# sam3u_breakout.net
KiCad netlist of a schematic drawn in EAGLE
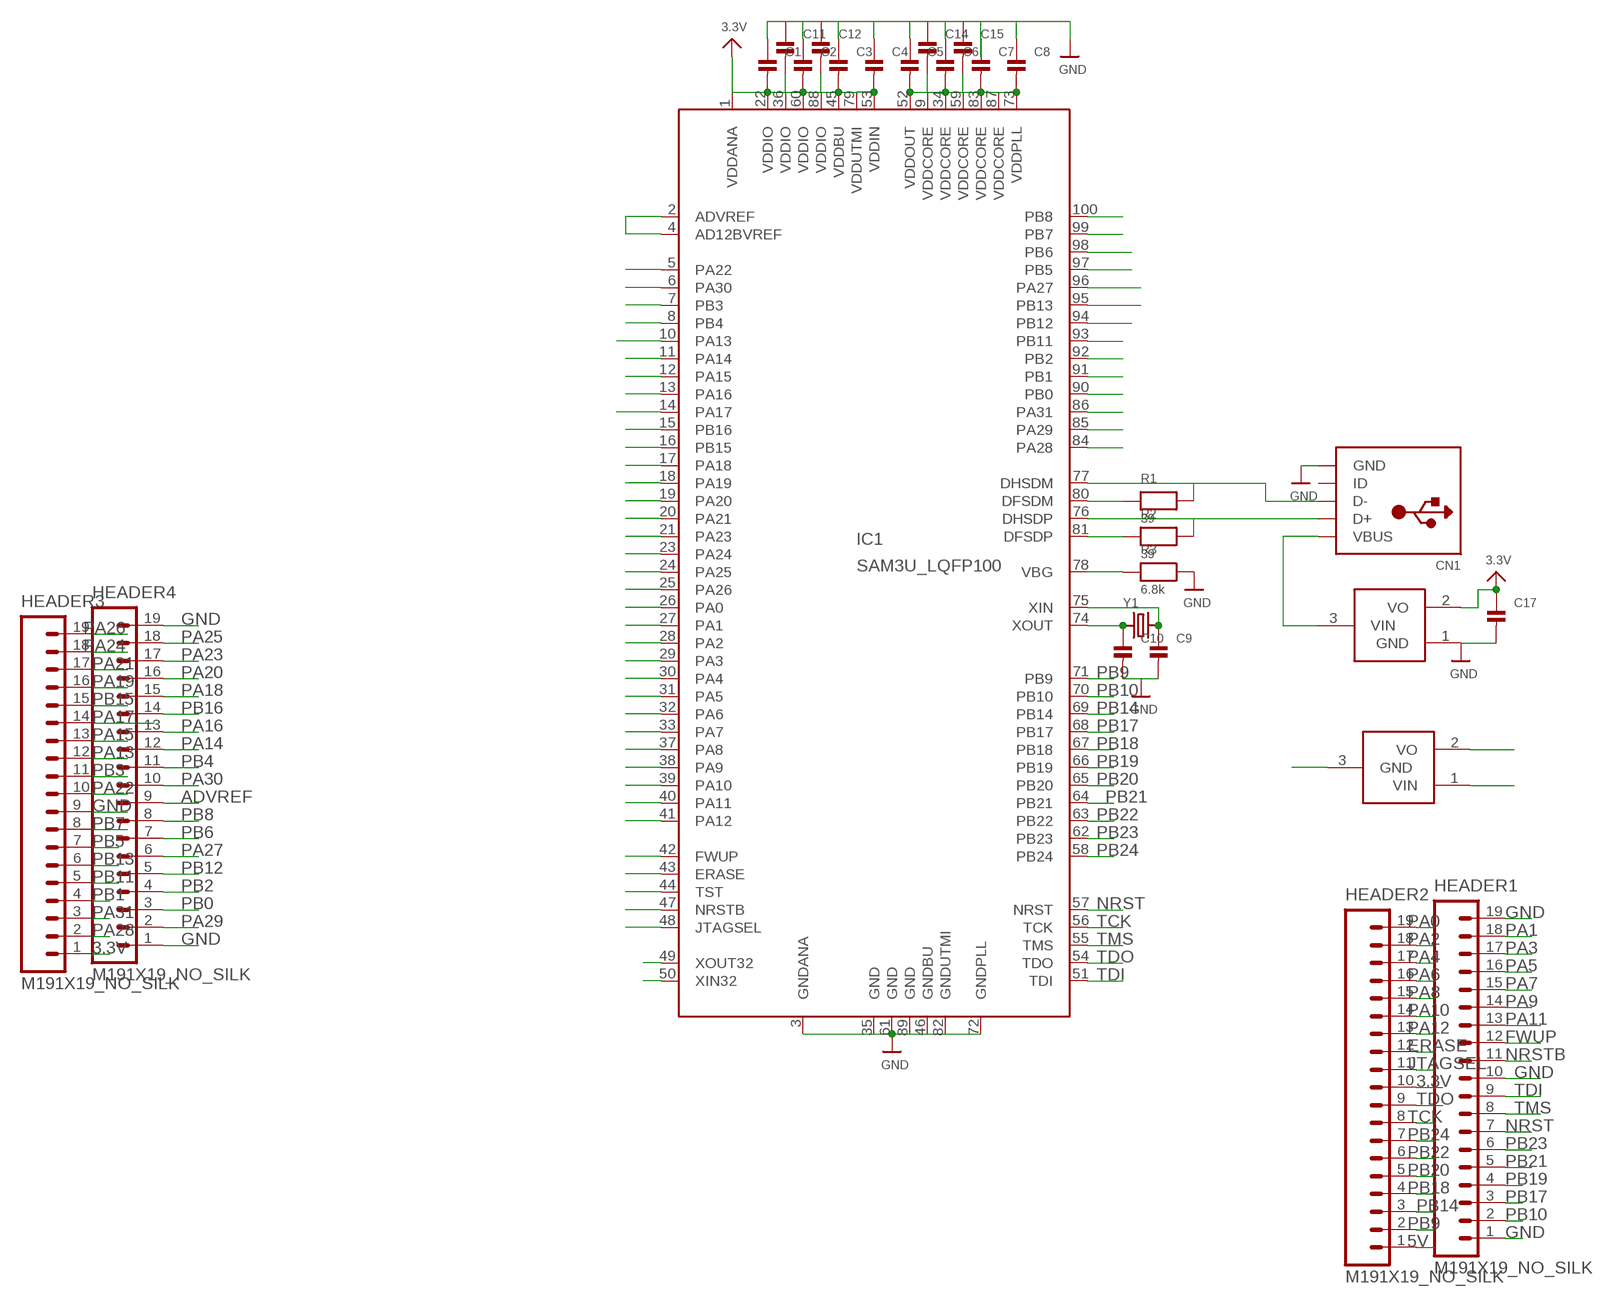
[diagram p0: schematic, sheet 1]

(export (version "E")
  (design (tool "Eeschema 10.0.6"))
  (components
    (comp (ref "C1")
      (value "CAP_CERAMIC0402")
      (footprint "eagle-import:0402")
      (libsource (lib "eagle-import") (part "CAP_CERAMIC0402"))
    )
    (comp (ref "C2")
      (value "CAP_CERAMIC0402")
      (footprint "eagle-import:0402")
      (libsource (lib "eagle-import") (part "CAP_CERAMIC0402"))
    )
    (comp (ref "C3")
      (value "CAP_CERAMIC0402")
      (footprint "eagle-import:0402")
      (libsource (lib "eagle-import") (part "CAP_CERAMIC0402"))
    )
    (comp (ref "C4")
      (value "CAP_CERAMIC0402")
      (footprint "eagle-import:0402")
      (libsource (lib "eagle-import") (part "CAP_CERAMIC0402"))
    )
    (comp (ref "C5")
      (value "CAP_CERAMIC0402")
      (footprint "eagle-import:0402")
      (libsource (lib "eagle-import") (part "CAP_CERAMIC0402"))
    )
    (comp (ref "C6")
      (value "CAP_CERAMIC0402")
      (footprint "eagle-import:0402")
      (libsource (lib "eagle-import") (part "CAP_CERAMIC0402"))
    )
    (comp (ref "C7")
      (value "CAP_CERAMIC0402")
      (footprint "eagle-import:0402")
      (libsource (lib "eagle-import") (part "CAP_CERAMIC0402"))
    )
    (comp (ref "C8")
      (value "CAP_CERAMIC0402")
      (footprint "eagle-import:0402")
      (libsource (lib "eagle-import") (part "CAP_CERAMIC0402"))
    )
    (comp (ref "C9")
      (value "CAP_CERAMIC0402")
      (footprint "eagle-import:0402")
      (libsource (lib "eagle-import") (part "CAP_CERAMIC0402"))
    )
    (comp (ref "C10")
      (value "CAP_CERAMIC0402")
      (footprint "eagle-import:0402")
      (libsource (lib "eagle-import") (part "CAP_CERAMIC0402"))
    )
    (comp (ref "C11")
      (value "CAP_CERAMIC0402")
      (footprint "eagle-import:0402")
      (libsource (lib "eagle-import") (part "CAP_CERAMIC0402"))
    )
    (comp (ref "C12")
      (value "CAP_CERAMIC0402")
      (footprint "eagle-import:0402")
      (libsource (lib "eagle-import") (part "CAP_CERAMIC0402"))
    )
    (comp (ref "C14")
      (value "CAP_CERAMIC0402")
      (footprint "eagle-import:0402")
      (libsource (lib "eagle-import") (part "CAP_CERAMIC0402"))
    )
    (comp (ref "C15")
      (value "CAP_CERAMIC0402")
      (footprint "eagle-import:0402")
      (libsource (lib "eagle-import") (part "CAP_CERAMIC0402"))
    )
    (comp (ref "C17")
      (value "CAP_CERAMIC0402")
      (footprint "eagle-import:0402")
      (libsource (lib "eagle-import") (part "CAP_CERAMIC0402"))
    )
    (comp (ref "CN1")
      (value "USBMICROB")
      (footprint "eagle-import:USB-MICROB")
      (libsource (lib "eagle-import") (part "USBMICROB"))
    )
    (comp (ref "HEADER1")
      (value "M191X19_NO_SILK")
      (footprint "eagle-import:1X19_NO_SILK")
      (libsource (lib "eagle-import") (part "M191X19_NO_SILK"))
    )
    (comp (ref "HEADER2")
      (value "M191X19_NO_SILK")
      (footprint "eagle-import:1X19_NO_SILK")
      (libsource (lib "eagle-import") (part "M191X19_NO_SILK"))
    )
    (comp (ref "HEADER3")
      (value "M191X19_NO_SILK")
      (footprint "eagle-import:1X19_NO_SILK")
      (libsource (lib "eagle-import") (part "M191X19_NO_SILK"))
    )
    (comp (ref "HEADER4")
      (value "M191X19_NO_SILK")
      (footprint "eagle-import:1X19_NO_SILK")
      (libsource (lib "eagle-import") (part "M191X19_NO_SILK"))
    )
    (comp (ref "IC1")
      (value "SAM3U_LQFP100")
      (footprint "eagle-import:LQFP100")
      (libsource (lib "eagle-import") (part "SAM3U_LQFP100"))
    )
    (comp (ref "R1")
      (value "39")
      (footprint "eagle-import:0603")
      (libsource (lib "eagle-import") (part "RESISTOR0603"))
    )
    (comp (ref "R2")
      (value "39")
      (footprint "eagle-import:0603")
      (libsource (lib "eagle-import") (part "RESISTOR0603"))
    )
    (comp (ref "R3")
      (value "6.8k")
      (footprint "eagle-import:0603")
      (libsource (lib "eagle-import") (part "RESISTOR0603"))
    )
    (comp (ref "U$7")
      (value "VREG")
      (footprint "eagle-import:SOT23-3")
      (libsource (lib "eagle-import") (part "VREG"))
    )
    (comp (ref "U$14")
      (value "VREF")
      (footprint "eagle-import:SOT23-3")
      (libsource (lib "eagle-import") (part "VREF"))
    )
    (comp (ref "Y1")
      (value "CRYSTALSMD")
      (footprint "eagle-import:HC49UP")
      (libsource (lib "eagle-import") (part "CRYSTALSMD"))
    )
  )
  (nets
    (net (code "1") (name "/5V") (class "Default")
      (node (ref "CN1") (pin "P1") (pinfunction "VBUS_P1") (pintype "power_in"))
      (node (ref "HEADER2") (pin "1") (pinfunction "1_1") (pintype "passive"))
      (node (ref "U$7") (pin "3") (pinfunction "VIN_3") (pintype "bidirectional"))
    )
    (net (code "2") (name "/ADVREF") (class "Default")
      (node (ref "HEADER4") (pin "9") (pinfunction "9_9") (pintype "passive"))
      (node (ref "IC1") (pin "2") (pinfunction "ADVREF_2") (pintype "power_in"))
      (node (ref "IC1") (pin "4") (pinfunction "AD12BVREF_4") (pintype "input"))
      (node (ref "U$14") (pin "2") (pinfunction "VO_2") (pintype "bidirectional"))
    )
    (net (code "3") (name "/ERASE") (class "Default")
      (node (ref "HEADER2") (pin "12") (pinfunction "12_12") (pintype "passive"))
      (node (ref "IC1") (pin "43") (pinfunction "ERASE_43") (pintype "passive"))
    )
    (net (code "4") (name "/FWUP") (class "Default")
      (node (ref "HEADER1") (pin "12") (pinfunction "12_12") (pintype "passive"))
      (node (ref "IC1") (pin "42") (pinfunction "FWUP_42") (pintype "passive"))
    )
    (net (code "5") (name "/JTAGSEL") (class "Default")
      (node (ref "HEADER2") (pin "11") (pinfunction "11_11") (pintype "passive"))
      (node (ref "IC1") (pin "48") (pinfunction "JTAGSEL_48") (pintype "input"))
    )
    (net (code "6") (name "/NRST") (class "Default")
      (node (ref "HEADER1") (pin "7") (pinfunction "7_7") (pintype "passive"))
      (node (ref "IC1") (pin "57") (pinfunction "NRST_57") (pintype "input"))
    )
    (net (code "7") (name "/NRSTB") (class "Default")
      (node (ref "HEADER1") (pin "11") (pinfunction "11_11") (pintype "passive"))
      (node (ref "IC1") (pin "47") (pinfunction "NRSTB_47") (pintype "passive"))
    )
    (net (code "8") (name "/PA0") (class "Default")
      (node (ref "HEADER2") (pin "19") (pinfunction "19_19") (pintype "passive"))
      (node (ref "IC1") (pin "26") (pinfunction "PA0_26") (pintype "bidirectional"))
    )
    (net (code "9") (name "/PA1") (class "Default")
      (node (ref "HEADER1") (pin "18") (pinfunction "18_18") (pintype "passive"))
      (node (ref "IC1") (pin "27") (pinfunction "PA1_27") (pintype "bidirectional"))
    )
    (net (code "10") (name "/PA2") (class "Default")
      (node (ref "HEADER2") (pin "18") (pinfunction "18_18") (pintype "passive"))
      (node (ref "IC1") (pin "28") (pinfunction "PA2_28") (pintype "bidirectional"))
    )
    (net (code "11") (name "/PA3") (class "Default")
      (node (ref "HEADER1") (pin "17") (pinfunction "17_17") (pintype "passive"))
      (node (ref "IC1") (pin "29") (pinfunction "PA3_29") (pintype "bidirectional"))
    )
    (net (code "12") (name "/PA4") (class "Default")
      (node (ref "HEADER2") (pin "17") (pinfunction "17_17") (pintype "passive"))
      (node (ref "IC1") (pin "30") (pinfunction "PA4_30") (pintype "bidirectional"))
    )
    (net (code "13") (name "/PA5") (class "Default")
      (node (ref "HEADER1") (pin "16") (pinfunction "16_16") (pintype "passive"))
      (node (ref "IC1") (pin "31") (pinfunction "PA5_31") (pintype "bidirectional"))
    )
    (net (code "14") (name "/PA6") (class "Default")
      (node (ref "HEADER2") (pin "16") (pinfunction "16_16") (pintype "passive"))
      (node (ref "IC1") (pin "32") (pinfunction "PA6_32") (pintype "bidirectional"))
    )
    (net (code "15") (name "/PA7") (class "Default")
      (node (ref "HEADER1") (pin "15") (pinfunction "15_15") (pintype "passive"))
      (node (ref "IC1") (pin "33") (pinfunction "PA7_33") (pintype "bidirectional"))
    )
    (net (code "16") (name "/PA8") (class "Default")
      (node (ref "HEADER2") (pin "15") (pinfunction "15_15") (pintype "passive"))
      (node (ref "IC1") (pin "37") (pinfunction "PA8_37") (pintype "bidirectional"))
    )
    (net (code "17") (name "/PA9") (class "Default")
      (node (ref "HEADER1") (pin "14") (pinfunction "14_14") (pintype "passive"))
      (node (ref "IC1") (pin "38") (pinfunction "PA9_38") (pintype "bidirectional"))
    )
    (net (code "18") (name "/PA10") (class "Default")
      (node (ref "HEADER2") (pin "14") (pinfunction "14_14") (pintype "passive"))
      (node (ref "IC1") (pin "39") (pinfunction "PA10_39") (pintype "bidirectional"))
    )
    (net (code "19") (name "/PA11") (class "Default")
      (node (ref "HEADER1") (pin "13") (pinfunction "13_13") (pintype "passive"))
      (node (ref "IC1") (pin "40") (pinfunction "PA11_40") (pintype "bidirectional"))
    )
    (net (code "20") (name "/PA12") (class "Default")
      (node (ref "HEADER2") (pin "13") (pinfunction "13_13") (pintype "passive"))
      (node (ref "IC1") (pin "41") (pinfunction "PA12_41") (pintype "bidirectional"))
    )
    (net (code "21") (name "/PA13") (class "Default")
      (node (ref "HEADER3") (pin "12") (pinfunction "12_12") (pintype "passive"))
      (node (ref "IC1") (pin "10") (pinfunction "PA13_10") (pintype "bidirectional"))
    )
    (net (code "22") (name "/PA14") (class "Default")
      (node (ref "HEADER4") (pin "12") (pinfunction "12_12") (pintype "passive"))
      (node (ref "IC1") (pin "11") (pinfunction "PA14_11") (pintype "bidirectional"))
    )
    (net (code "23") (name "/PA15") (class "Default")
      (node (ref "HEADER3") (pin "13") (pinfunction "13_13") (pintype "passive"))
      (node (ref "IC1") (pin "12") (pinfunction "PA15_12") (pintype "bidirectional"))
    )
    (net (code "24") (name "/PA16") (class "Default")
      (node (ref "HEADER4") (pin "13") (pinfunction "13_13") (pintype "passive"))
      (node (ref "IC1") (pin "13") (pinfunction "PA16_13") (pintype "bidirectional"))
    )
    (net (code "25") (name "/PA17") (class "Default")
      (node (ref "HEADER3") (pin "14") (pinfunction "14_14") (pintype "passive"))
      (node (ref "IC1") (pin "14") (pinfunction "PA17_14") (pintype "bidirectional"))
    )
    (net (code "26") (name "/PA18") (class "Default")
      (node (ref "HEADER4") (pin "15") (pinfunction "15_15") (pintype "passive"))
      (node (ref "IC1") (pin "17") (pinfunction "PA18_17") (pintype "bidirectional"))
    )
    (net (code "27") (name "/PA19") (class "Default")
      (node (ref "HEADER3") (pin "16") (pinfunction "16_16") (pintype "passive"))
      (node (ref "IC1") (pin "18") (pinfunction "PA19_18") (pintype "bidirectional"))
    )
    (net (code "28") (name "/PA20") (class "Default")
      (node (ref "HEADER4") (pin "16") (pinfunction "16_16") (pintype "passive"))
      (node (ref "IC1") (pin "19") (pinfunction "PA20_19") (pintype "bidirectional"))
    )
    (net (code "29") (name "/PA21") (class "Default")
      (node (ref "HEADER3") (pin "17") (pinfunction "17_17") (pintype "passive"))
      (node (ref "IC1") (pin "20") (pinfunction "PA21_20") (pintype "bidirectional"))
    )
    (net (code "30") (name "/PA22") (class "Default")
      (node (ref "HEADER3") (pin "10") (pinfunction "10_10") (pintype "passive"))
      (node (ref "IC1") (pin "5") (pinfunction "PA22_5") (pintype "bidirectional"))
    )
    (net (code "31") (name "/PA23") (class "Default")
      (node (ref "HEADER4") (pin "17") (pinfunction "17_17") (pintype "passive"))
      (node (ref "IC1") (pin "21") (pinfunction "PA23_21") (pintype "bidirectional"))
    )
    (net (code "32") (name "/PA24") (class "Default")
      (node (ref "HEADER3") (pin "18") (pinfunction "18_18") (pintype "passive"))
      (node (ref "IC1") (pin "23") (pinfunction "PA24_23") (pintype "bidirectional"))
    )
    (net (code "33") (name "/PA25") (class "Default")
      (node (ref "HEADER4") (pin "18") (pinfunction "18_18") (pintype "passive"))
      (node (ref "IC1") (pin "24") (pinfunction "PA25_24") (pintype "bidirectional"))
    )
    (net (code "34") (name "/PA26") (class "Default")
      (node (ref "HEADER3") (pin "19") (pinfunction "19_19") (pintype "passive"))
      (node (ref "IC1") (pin "25") (pinfunction "PA26_25") (pintype "bidirectional"))
    )
    (net (code "35") (name "/PA27") (class "Default")
      (node (ref "HEADER4") (pin "6") (pinfunction "6_6") (pintype "passive"))
      (node (ref "IC1") (pin "96") (pinfunction "PA27_96") (pintype "bidirectional"))
    )
    (net (code "36") (name "/PA28") (class "Default")
      (node (ref "HEADER3") (pin "2") (pinfunction "2_2") (pintype "passive"))
      (node (ref "IC1") (pin "84") (pinfunction "PA28_84") (pintype "bidirectional"))
    )
    (net (code "37") (name "/PA29") (class "Default")
      (node (ref "HEADER4") (pin "2") (pinfunction "2_2") (pintype "passive"))
      (node (ref "IC1") (pin "85") (pinfunction "PA29_85") (pintype "bidirectional"))
    )
    (net (code "38") (name "/PA30") (class "Default")
      (node (ref "HEADER4") (pin "10") (pinfunction "10_10") (pintype "passive"))
      (node (ref "IC1") (pin "6") (pinfunction "PA30_6") (pintype "bidirectional"))
    )
    (net (code "39") (name "/PA31") (class "Default")
      (node (ref "HEADER3") (pin "3") (pinfunction "3_3") (pintype "passive"))
      (node (ref "IC1") (pin "86") (pinfunction "PA31_86") (pintype "bidirectional"))
    )
    (net (code "40") (name "/PB0") (class "Default")
      (node (ref "HEADER4") (pin "3") (pinfunction "3_3") (pintype "passive"))
      (node (ref "IC1") (pin "90") (pinfunction "PB0_90") (pintype "bidirectional"))
    )
    (net (code "41") (name "/PB1") (class "Default")
      (node (ref "HEADER3") (pin "4") (pinfunction "4_4") (pintype "passive"))
      (node (ref "IC1") (pin "91") (pinfunction "PB1_91") (pintype "bidirectional"))
    )
    (net (code "42") (name "/PB2") (class "Default")
      (node (ref "HEADER4") (pin "4") (pinfunction "4_4") (pintype "passive"))
      (node (ref "IC1") (pin "92") (pinfunction "PB2_92") (pintype "bidirectional"))
    )
    (net (code "43") (name "/PB3") (class "Default")
      (node (ref "HEADER3") (pin "11") (pinfunction "11_11") (pintype "passive"))
      (node (ref "IC1") (pin "7") (pinfunction "PB3_7") (pintype "bidirectional"))
    )
    (net (code "44") (name "/PB4") (class "Default")
      (node (ref "HEADER4") (pin "11") (pinfunction "11_11") (pintype "passive"))
      (node (ref "IC1") (pin "8") (pinfunction "PB4_8") (pintype "bidirectional"))
    )
    (net (code "45") (name "/PB5") (class "Default")
      (node (ref "HEADER3") (pin "7") (pinfunction "7_7") (pintype "passive"))
      (node (ref "IC1") (pin "97") (pinfunction "PB5_97") (pintype "bidirectional"))
    )
    (net (code "46") (name "/PB6") (class "Default")
      (node (ref "HEADER4") (pin "7") (pinfunction "7_7") (pintype "passive"))
      (node (ref "IC1") (pin "98") (pinfunction "PB6_98") (pintype "bidirectional"))
    )
    (net (code "47") (name "/PB7") (class "Default")
      (node (ref "HEADER3") (pin "8") (pinfunction "8_8") (pintype "passive"))
      (node (ref "IC1") (pin "99") (pinfunction "PB7_99") (pintype "bidirectional"))
    )
    (net (code "48") (name "/PB8") (class "Default")
      (node (ref "HEADER4") (pin "8") (pinfunction "8_8") (pintype "passive"))
      (node (ref "IC1") (pin "100") (pinfunction "PB8_100") (pintype "bidirectional"))
    )
    (net (code "49") (name "/PB9") (class "Default")
      (node (ref "HEADER2") (pin "2") (pinfunction "2_2") (pintype "passive"))
      (node (ref "IC1") (pin "71") (pinfunction "PB9_71") (pintype "bidirectional"))
    )
    (net (code "50") (name "/PB10") (class "Default")
      (node (ref "HEADER1") (pin "2") (pinfunction "2_2") (pintype "passive"))
      (node (ref "IC1") (pin "70") (pinfunction "PB10_70") (pintype "bidirectional"))
    )
    (net (code "51") (name "/PB11") (class "Default")
      (node (ref "HEADER3") (pin "5") (pinfunction "5_5") (pintype "passive"))
      (node (ref "IC1") (pin "93") (pinfunction "PB11_93") (pintype "bidirectional"))
    )
    (net (code "52") (name "/PB12") (class "Default")
      (node (ref "HEADER4") (pin "5") (pinfunction "5_5") (pintype "passive"))
      (node (ref "IC1") (pin "94") (pinfunction "PB12_94") (pintype "bidirectional"))
    )
    (net (code "53") (name "/PB13") (class "Default")
      (node (ref "HEADER3") (pin "6") (pinfunction "6_6") (pintype "passive"))
      (node (ref "IC1") (pin "95") (pinfunction "PB13_95") (pintype "bidirectional"))
    )
    (net (code "54") (name "/PB14") (class "Default")
      (node (ref "HEADER2") (pin "3") (pinfunction "3_3") (pintype "passive"))
      (node (ref "IC1") (pin "69") (pinfunction "PB14_69") (pintype "bidirectional"))
    )
    (net (code "55") (name "/PB15") (class "Default")
      (node (ref "HEADER3") (pin "15") (pinfunction "15_15") (pintype "passive"))
      (node (ref "IC1") (pin "16") (pinfunction "PB15_16") (pintype "bidirectional"))
    )
    (net (code "56") (name "/PB16") (class "Default")
      (node (ref "HEADER4") (pin "14") (pinfunction "14_14") (pintype "passive"))
      (node (ref "IC1") (pin "15") (pinfunction "PB16_15") (pintype "bidirectional"))
    )
    (net (code "57") (name "/PB17") (class "Default")
      (node (ref "HEADER1") (pin "3") (pinfunction "3_3") (pintype "passive"))
      (node (ref "IC1") (pin "68") (pinfunction "PB17_68") (pintype "bidirectional"))
    )
    (net (code "58") (name "/PB18") (class "Default")
      (node (ref "HEADER2") (pin "4") (pinfunction "4_4") (pintype "passive"))
      (node (ref "IC1") (pin "67") (pinfunction "PB18_67") (pintype "bidirectional"))
    )
    (net (code "59") (name "/PB19") (class "Default")
      (node (ref "HEADER1") (pin "4") (pinfunction "4_4") (pintype "passive"))
      (node (ref "IC1") (pin "66") (pinfunction "PB19_66") (pintype "bidirectional"))
    )
    (net (code "60") (name "/PB20") (class "Default")
      (node (ref "HEADER2") (pin "5") (pinfunction "5_5") (pintype "passive"))
      (node (ref "IC1") (pin "65") (pinfunction "PB20_65") (pintype "bidirectional"))
    )
    (net (code "61") (name "/PB21") (class "Default")
      (node (ref "HEADER1") (pin "5") (pinfunction "5_5") (pintype "passive"))
      (node (ref "IC1") (pin "64") (pinfunction "PB21_64") (pintype "bidirectional"))
    )
    (net (code "62") (name "/PB22") (class "Default")
      (node (ref "HEADER2") (pin "6") (pinfunction "6_6") (pintype "passive"))
      (node (ref "IC1") (pin "63") (pinfunction "PB22_63") (pintype "bidirectional"))
    )
    (net (code "63") (name "/PB23") (class "Default")
      (node (ref "HEADER1") (pin "6") (pinfunction "6_6") (pintype "passive"))
      (node (ref "IC1") (pin "62") (pinfunction "PB23_62") (pintype "bidirectional"))
    )
    (net (code "64") (name "/PB24") (class "Default")
      (node (ref "HEADER2") (pin "7") (pinfunction "7_7") (pintype "passive"))
      (node (ref "IC1") (pin "58") (pinfunction "PB24_58") (pintype "bidirectional"))
    )
    (net (code "65") (name "/TCK") (class "Default")
      (node (ref "HEADER2") (pin "8") (pinfunction "8_8") (pintype "passive"))
      (node (ref "IC1") (pin "56") (pinfunction "TCK_56") (pintype "input"))
    )
    (net (code "66") (name "/TDI") (class "Default")
      (node (ref "HEADER1") (pin "9") (pinfunction "9_9") (pintype "passive"))
      (node (ref "IC1") (pin "51") (pinfunction "TDI_51") (pintype "input"))
    )
    (net (code "67") (name "/TDO") (class "Default")
      (node (ref "HEADER2") (pin "9") (pinfunction "9_9") (pintype "passive"))
      (node (ref "IC1") (pin "54") (pinfunction "TDO_54") (pintype "output"))
    )
    (net (code "68") (name "/TMS") (class "Default")
      (node (ref "HEADER1") (pin "8") (pinfunction "8_8") (pintype "passive"))
      (node (ref "IC1") (pin "55") (pinfunction "TMS_55") (pintype "input"))
    )
    (net (code "69") (name "3.3V") (class "Default")
      (node (ref "C1") (pin "2") (pinfunction "P$2_2") (pintype "passive"))
      (node (ref "C11") (pin "2") (pinfunction "P$2_2") (pintype "passive"))
      (node (ref "C12") (pin "2") (pinfunction "P$2_2") (pintype "passive"))
      (node (ref "C17") (pin "1") (pinfunction "P$1_1") (pintype "passive"))
      (node (ref "C2") (pin "2") (pinfunction "P$2_2") (pintype "passive"))
      (node (ref "C3") (pin "2") (pinfunction "P$2_2") (pintype "passive"))
      (node (ref "C4") (pin "2") (pinfunction "P$2_2") (pintype "passive"))
      (node (ref "HEADER2") (pin "10") (pinfunction "10_10") (pintype "passive"))
      (node (ref "HEADER3") (pin "1") (pinfunction "1_1") (pintype "passive"))
      (node (ref "IC1") (pin "1") (pinfunction "VDDANA_1") (pintype "power_in"))
      (node (ref "IC1") (pin "22") (pinfunction "VDDIO_22") (pintype "power_in"))
      (node (ref "IC1") (pin "36") (pinfunction "VDDIO_36") (pintype "power_in"))
      (node (ref "IC1") (pin "45") (pinfunction "VDDBU_45") (pintype "power_in"))
      (node (ref "IC1") (pin "53") (pinfunction "VDDIN_53") (pintype "power_in"))
      (node (ref "IC1") (pin "60") (pinfunction "VDDIO_60") (pintype "power_in"))
      (node (ref "IC1") (pin "79") (pinfunction "VDDUTMI_79") (pintype "power_in"))
      (node (ref "IC1") (pin "88") (pinfunction "VDDIO_88") (pintype "power_in"))
      (node (ref "U$14") (pin "1") (pinfunction "VIN_1") (pintype "bidirectional"))
      (node (ref "U$7") (pin "2") (pinfunction "VO_2") (pintype "bidirectional"))
    )
    (net (code "70") (name "GND") (class "Default")
      (node (ref "C1") (pin "1") (pinfunction "P$1_1") (pintype "passive"))
      (node (ref "C10") (pin "2") (pinfunction "P$2_2") (pintype "passive"))
      (node (ref "C11") (pin "1") (pinfunction "P$1_1") (pintype "passive"))
      (node (ref "C12") (pin "1") (pinfunction "P$1_1") (pintype "passive"))
      (node (ref "C14") (pin "1") (pinfunction "P$1_1") (pintype "passive"))
      (node (ref "C15") (pin "1") (pinfunction "P$1_1") (pintype "passive"))
      (node (ref "C17") (pin "2") (pinfunction "P$2_2") (pintype "passive"))
      (node (ref "C2") (pin "1") (pinfunction "P$1_1") (pintype "passive"))
      (node (ref "C3") (pin "1") (pinfunction "P$1_1") (pintype "passive"))
      (node (ref "C4") (pin "1") (pinfunction "P$1_1") (pintype "passive"))
      (node (ref "C5") (pin "1") (pinfunction "P$1_1") (pintype "passive"))
      (node (ref "C6") (pin "1") (pinfunction "P$1_1") (pintype "passive"))
      (node (ref "C8") (pin "1") (pinfunction "P$1_1") (pintype "passive"))
      (node (ref "C9") (pin "2") (pinfunction "P$2_2") (pintype "passive"))
      (node (ref "CN1") (pin "P5") (pinfunction "GND_P5") (pintype "power_in"))
      (node (ref "HEADER1") (pin "1") (pinfunction "1_1") (pintype "passive"))
      (node (ref "HEADER1") (pin "10") (pinfunction "10_10") (pintype "passive"))
      (node (ref "HEADER1") (pin "19") (pinfunction "19_19") (pintype "passive"))
      (node (ref "HEADER3") (pin "9") (pinfunction "9_9") (pintype "passive"))
      (node (ref "HEADER4") (pin "1") (pinfunction "1_1") (pintype "passive"))
      (node (ref "HEADER4") (pin "19") (pinfunction "19_19") (pintype "passive"))
      (node (ref "IC1") (pin "3") (pinfunction "GNDANA_3") (pintype "power_in"))
      (node (ref "IC1") (pin "35") (pinfunction "GND_35") (pintype "power_in"))
      (node (ref "IC1") (pin "46") (pinfunction "GNDBU_46") (pintype "power_in"))
      (node (ref "IC1") (pin "61") (pinfunction "GND_61") (pintype "power_in"))
      (node (ref "IC1") (pin "72") (pinfunction "GNDPLL_72") (pintype "power_in"))
      (node (ref "IC1") (pin "82") (pinfunction "GNDUTMI_82") (pintype "power_in"))
      (node (ref "IC1") (pin "89") (pinfunction "GND_89") (pintype "power_in"))
      (node (ref "R3") (pin "2") (pinfunction "2_2") (pintype "passive"))
      (node (ref "U$14") (pin "3") (pinfunction "GND_3") (pintype "bidirectional"))
      (node (ref "U$7") (pin "1") (pinfunction "GND_1") (pintype "bidirectional"))
    )
    (net (code "71") (name "Net-(C9-P$1)") (class "Default")
      (node (ref "C9") (pin "1") (pinfunction "P$1_1") (pintype "passive"))
      (node (ref "IC1") (pin "75") (pinfunction "XIN_75") (pintype "passive"))
      (node (ref "Y1") (pin "2") (pinfunction "2_2") (pintype "passive"))
    )
    (net (code "72") (name "Net-(C10-P$1)") (class "Default")
      (node (ref "C10") (pin "1") (pinfunction "P$1_1") (pintype "passive"))
      (node (ref "IC1") (pin "74") (pinfunction "XOUT_74") (pintype "passive"))
      (node (ref "Y1") (pin "1") (pinfunction "1_1") (pintype "passive"))
    )
    (net (code "73") (name "Net-(C14-P$2)") (class "Default")
      (node (ref "C14") (pin "2") (pinfunction "P$2_2") (pintype "passive"))
      (node (ref "C15") (pin "2") (pinfunction "P$2_2") (pintype "passive"))
      (node (ref "C5") (pin "2") (pinfunction "P$2_2") (pintype "passive"))
      (node (ref "C6") (pin "2") (pinfunction "P$2_2") (pintype "passive"))
      (node (ref "C7") (pin "2") (pinfunction "P$2_2") (pintype "passive"))
      (node (ref "C8") (pin "2") (pinfunction "P$2_2") (pintype "passive"))
      (node (ref "IC1") (pin "34") (pinfunction "VDDCORE_34") (pintype "power_in"))
      (node (ref "IC1") (pin "52") (pinfunction "VDDOUT_52") (pintype "power_in"))
      (node (ref "IC1") (pin "59") (pinfunction "VDDCORE_59") (pintype "power_in"))
      (node (ref "IC1") (pin "73") (pinfunction "VDDPLL_73") (pintype "power_in"))
      (node (ref "IC1") (pin "83") (pinfunction "VDDCORE_83") (pintype "power_in"))
      (node (ref "IC1") (pin "87") (pinfunction "VDDCORE_87") (pintype "power_in"))
      (node (ref "IC1") (pin "9") (pinfunction "VDDCORE_9") (pintype "power_in"))
    )
    (net (code "74") (name "Net-(CN1-D+)") (class "Default")
      (node (ref "CN1") (pin "P3") (pinfunction "D+_P3") (pintype "bidirectional"))
      (node (ref "IC1") (pin "76") (pinfunction "DHSDP_76") (pintype "passive"))
      (node (ref "R2") (pin "2") (pinfunction "2_2") (pintype "passive"))
    )
    (net (code "75") (name "Net-(CN1-D-)") (class "Default")
      (node (ref "CN1") (pin "P2") (pinfunction "D-_P2") (pintype "bidirectional"))
      (node (ref "IC1") (pin "77") (pinfunction "DHSDM_77") (pintype "passive"))
      (node (ref "R1") (pin "2") (pinfunction "2_2") (pintype "passive"))
    )
    (net (code "76") (name "Net-(IC1-DFSDM)") (class "Default")
      (node (ref "IC1") (pin "80") (pinfunction "DFSDM_80") (pintype "passive"))
      (node (ref "R1") (pin "1") (pinfunction "1_1") (pintype "passive"))
    )
    (net (code "77") (name "Net-(IC1-DFSDP)") (class "Default")
      (node (ref "IC1") (pin "81") (pinfunction "DFSDP_81") (pintype "passive"))
      (node (ref "R2") (pin "1") (pinfunction "1_1") (pintype "passive"))
    )
    (net (code "78") (name "Net-(IC1-VBG)") (class "Default")
      (node (ref "IC1") (pin "78") (pinfunction "VBG_78") (pintype "power_in"))
      (node (ref "R3") (pin "1") (pinfunction "1_1") (pintype "passive"))
    )
    (net (code "79") (name "unconnected-(C7-P$1-Pad1)") (class "Default")
      (node (ref "C7") (pin "1") (pinfunction "P$1_1") (pintype "passive"))
    )
    (net (code "80") (name "unconnected-(CN1-ID-PadP4)") (class "Default")
      (node (ref "CN1") (pin "P4") (pinfunction "ID_P4") (pintype "bidirectional"))
    )
    (net (code "81") (name "unconnected-(IC1-TST-Pad44)") (class "Default")
      (node (ref "IC1") (pin "44") (pinfunction "TST_44") (pintype "input"))
    )
    (net (code "82") (name "unconnected-(IC1-XIN32-Pad50)") (class "Default")
      (node (ref "IC1") (pin "50") (pinfunction "XIN32_50") (pintype "passive"))
    )
    (net (code "83") (name "unconnected-(IC1-XOUT32-Pad49)") (class "Default")
      (node (ref "IC1") (pin "49") (pinfunction "XOUT32_49") (pintype "passive"))
    )
  )
)
